# Teensy-Maxuino-Slave-A4988-stepper_shiel.net
KiCad netlist of a schematic drawn in EAGLE
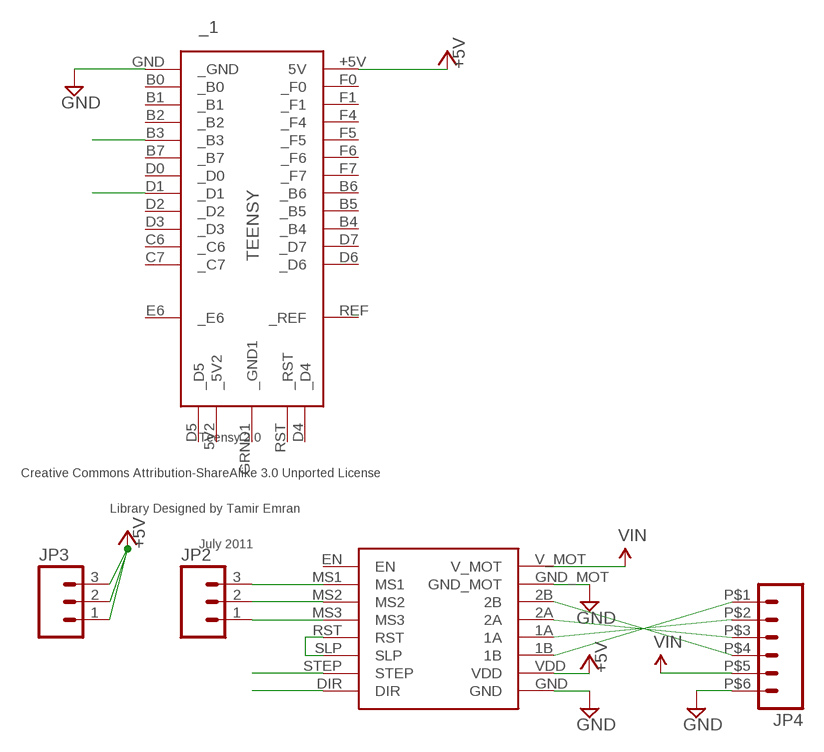
[diagram p0: schematic, sheet 1]

(export (version "E")
  (design (tool "Eeschema 10.0.6"))
  (components
    (comp (ref "JP2")
      (value "M03PTH")
      (footprint "eagle-import:1X03")
      (libsource (lib "eagle-import") (part "M03PTH"))
    )
    (comp (ref "JP3")
      (value "M03PTH")
      (footprint "eagle-import:1X03")
      (libsource (lib "eagle-import") (part "M03PTH"))
    )
    (comp (ref "JP4")
      (value "M06")
      (footprint "eagle-import:SPRINGTERMINAL-2.54MM-6")
      (libsource (lib "eagle-import") (part "M06"))
    )
    (comp (ref "U$1")
      (value "POLOLU_A4988")
      (footprint "eagle-import:POLOLU_A4988")
      (libsource (lib "eagle-import") (part "POLOLU_A4988"))
    )
    (comp (ref "_1")
      (value "TEENSY")
      (footprint "eagle-import:TEENSY")
      (libsource (lib "eagle-import") (part "TEENSY"))
    )
  )
  (nets
    (net (code "1") (name "+5V") (class "Default")
      (node (ref "JP3") (pin "1") (pinfunction "1_1") (pintype "passive"))
      (node (ref "JP3") (pin "2") (pinfunction "2_2") (pintype "passive"))
      (node (ref "JP3") (pin "3") (pinfunction "3_3") (pintype "passive"))
      (node (ref "U$1") (pin "VDD") (pinfunction "VDD_VDD") (pintype "bidirectional"))
      (node (ref "_1") (pin "+5V") (pinfunction "5V_+5V") (pintype "bidirectional"))
    )
    (net (code "2") (name "/DIR") (class "Default")
      (node (ref "U$1") (pin "DIR") (pinfunction "DIR_DIR") (pintype "bidirectional"))
      (node (ref "_1") (pin "D1") (pinfunction "_D1_D1") (pintype "bidirectional"))
    )
    (net (code "3") (name "/STEP") (class "Default")
      (node (ref "U$1") (pin "STEP") (pinfunction "STEP_STEP") (pintype "bidirectional"))
      (node (ref "_1") (pin "B3") (pinfunction "_B3_B3") (pintype "bidirectional"))
    )
    (net (code "4") (name "GND") (class "Default")
      (node (ref "JP4") (pin "P$6") (pinfunction "6_P$6") (pintype "passive"))
      (node (ref "U$1") (pin "GND") (pinfunction "GND_GND") (pintype "bidirectional"))
      (node (ref "U$1") (pin "GND_MOT") (pinfunction "GND_MOT_GND_MOT") (pintype "bidirectional"))
      (node (ref "_1") (pin "GND") (pinfunction "_GND_GND") (pintype "bidirectional"))
    )
    (net (code "5") (name "Net-(JP2-Pad1)") (class "Default")
      (node (ref "JP2") (pin "1") (pinfunction "1_1") (pintype "passive"))
      (node (ref "U$1") (pin "MS3") (pinfunction "MS3_MS3") (pintype "bidirectional"))
    )
    (net (code "6") (name "Net-(JP2-Pad2)") (class "Default")
      (node (ref "JP2") (pin "2") (pinfunction "2_2") (pintype "passive"))
      (node (ref "U$1") (pin "MS2") (pinfunction "MS2_MS2") (pintype "bidirectional"))
    )
    (net (code "7") (name "Net-(JP2-Pad3)") (class "Default")
      (node (ref "JP2") (pin "3") (pinfunction "3_3") (pintype "passive"))
      (node (ref "U$1") (pin "MS1") (pinfunction "MS1_MS1") (pintype "bidirectional"))
    )
    (net (code "8") (name "Net-(JP4-1)") (class "Default")
      (node (ref "JP4") (pin "P$1") (pinfunction "1_P$1") (pintype "passive"))
      (node (ref "U$1") (pin "1B") (pinfunction "1B_1B") (pintype "bidirectional"))
    )
    (net (code "9") (name "Net-(JP4-2)") (class "Default")
      (node (ref "JP4") (pin "P$2") (pinfunction "2_P$2") (pintype "passive"))
      (node (ref "U$1") (pin "1A") (pinfunction "1A_1A") (pintype "bidirectional"))
    )
    (net (code "10") (name "Net-(JP4-3)") (class "Default")
      (node (ref "JP4") (pin "P$3") (pinfunction "3_P$3") (pintype "passive"))
      (node (ref "U$1") (pin "2A") (pinfunction "2A_2A") (pintype "bidirectional"))
    )
    (net (code "11") (name "Net-(JP4-4)") (class "Default")
      (node (ref "JP4") (pin "P$4") (pinfunction "4_P$4") (pintype "passive"))
      (node (ref "U$1") (pin "2B") (pinfunction "2B_2B") (pintype "bidirectional"))
    )
    (net (code "12") (name "Net-(U$1-PadRST)") (class "Default")
      (node (ref "U$1") (pin "RST") (pinfunction "RST_RST") (pintype "bidirectional"))
      (node (ref "U$1") (pin "SLP") (pinfunction "SLP_SLP") (pintype "bidirectional"))
    )
    (net (code "13") (name "VIN") (class "Default")
      (node (ref "JP4") (pin "P$5") (pinfunction "5_P$5") (pintype "passive"))
      (node (ref "U$1") (pin "V_MOT") (pinfunction "V_MOT_V_MOT") (pintype "bidirectional"))
    )
    (net (code "14") (name "unconnected-(U$1-PadEN)") (class "Default")
      (node (ref "U$1") (pin "EN") (pinfunction "EN_EN") (pintype "bidirectional"))
    )
    (net (code "15") (name "unconnected-(_1-_5V2-Pad5V2)") (class "Default")
      (node (ref "_1") (pin "5V2") (pinfunction "_5V2_5V2") (pintype "bidirectional"))
    )
    (net (code "16") (name "unconnected-(_1-_B0-PadB0)") (class "Default")
      (node (ref "_1") (pin "B0") (pinfunction "_B0_B0") (pintype "bidirectional"))
    )
    (net (code "17") (name "unconnected-(_1-_B1-PadB1)") (class "Default")
      (node (ref "_1") (pin "B1") (pinfunction "_B1_B1") (pintype "bidirectional"))
    )
    (net (code "18") (name "unconnected-(_1-_B2-PadB2)") (class "Default")
      (node (ref "_1") (pin "B2") (pinfunction "_B2_B2") (pintype "bidirectional"))
    )
    (net (code "19") (name "unconnected-(_1-_B4-PadB4)") (class "Default")
      (node (ref "_1") (pin "B4") (pinfunction "_B4_B4") (pintype "bidirectional"))
    )
    (net (code "20") (name "unconnected-(_1-_B5-PadB5)") (class "Default")
      (node (ref "_1") (pin "B5") (pinfunction "_B5_B5") (pintype "bidirectional"))
    )
    (net (code "21") (name "unconnected-(_1-_B6-PadB6)") (class "Default")
      (node (ref "_1") (pin "B6") (pinfunction "_B6_B6") (pintype "bidirectional"))
    )
    (net (code "22") (name "unconnected-(_1-_B7-PadB7)") (class "Default")
      (node (ref "_1") (pin "B7") (pinfunction "_B7_B7") (pintype "bidirectional"))
    )
    (net (code "23") (name "unconnected-(_1-_C6-PadC6)") (class "Default")
      (node (ref "_1") (pin "C6") (pinfunction "_C6_C6") (pintype "bidirectional"))
    )
    (net (code "24") (name "unconnected-(_1-_C7-PadC7)") (class "Default")
      (node (ref "_1") (pin "C7") (pinfunction "_C7_C7") (pintype "bidirectional"))
    )
    (net (code "25") (name "unconnected-(_1-_D0-PadD0)") (class "Default")
      (node (ref "_1") (pin "D0") (pinfunction "_D0_D0") (pintype "bidirectional"))
    )
    (net (code "26") (name "unconnected-(_1-_D2-PadD2)") (class "Default")
      (node (ref "_1") (pin "D2") (pinfunction "_D2_D2") (pintype "bidirectional"))
    )
    (net (code "27") (name "unconnected-(_1-_D3-PadD3)") (class "Default")
      (node (ref "_1") (pin "D3") (pinfunction "_D3_D3") (pintype "bidirectional"))
    )
    (net (code "28") (name "unconnected-(_1-_D4-PadD4)") (class "Default")
      (node (ref "_1") (pin "D4") (pinfunction "_D4_D4") (pintype "bidirectional"))
    )
    (net (code "29") (name "unconnected-(_1-_D5-PadD5)") (class "Default")
      (node (ref "_1") (pin "D5") (pinfunction "_D5_D5") (pintype "bidirectional"))
    )
    (net (code "30") (name "unconnected-(_1-_D6-PadD6)") (class "Default")
      (node (ref "_1") (pin "D6") (pinfunction "_D6_D6") (pintype "bidirectional"))
    )
    (net (code "31") (name "unconnected-(_1-_D7-PadD7)") (class "Default")
      (node (ref "_1") (pin "D7") (pinfunction "_D7_D7") (pintype "bidirectional"))
    )
    (net (code "32") (name "unconnected-(_1-_E6-PadE6)") (class "Default")
      (node (ref "_1") (pin "E6") (pinfunction "_E6_E6") (pintype "bidirectional"))
    )
    (net (code "33") (name "unconnected-(_1-_F0-PadF0)") (class "Default")
      (node (ref "_1") (pin "F0") (pinfunction "_F0_F0") (pintype "bidirectional"))
    )
    (net (code "34") (name "unconnected-(_1-_F1-PadF1)") (class "Default")
      (node (ref "_1") (pin "F1") (pinfunction "_F1_F1") (pintype "bidirectional"))
    )
    (net (code "35") (name "unconnected-(_1-_F4-PadF4)") (class "Default")
      (node (ref "_1") (pin "F4") (pinfunction "_F4_F4") (pintype "bidirectional"))
    )
    (net (code "36") (name "unconnected-(_1-_F5-PadF5)") (class "Default")
      (node (ref "_1") (pin "F5") (pinfunction "_F5_F5") (pintype "bidirectional"))
    )
    (net (code "37") (name "unconnected-(_1-_F6-PadF6)") (class "Default")
      (node (ref "_1") (pin "F6") (pinfunction "_F6_F6") (pintype "bidirectional"))
    )
    (net (code "38") (name "unconnected-(_1-_F7-PadF7)") (class "Default")
      (node (ref "_1") (pin "F7") (pinfunction "_F7_F7") (pintype "bidirectional"))
    )
    (net (code "39") (name "unconnected-(_1-_GND1-PadGRND1)") (class "Default")
      (node (ref "_1") (pin "GRND1") (pinfunction "_GND1_GRND1") (pintype "bidirectional"))
    )
    (net (code "40") (name "unconnected-(_1-_REF-PadREF)") (class "Default")
      (node (ref "_1") (pin "REF") (pinfunction "_REF_REF") (pintype "bidirectional"))
    )
    (net (code "41") (name "unconnected-(_1-_RST-PadRST)") (class "Default")
      (node (ref "_1") (pin "RST") (pinfunction "_RST_RST") (pintype "bidirectional"))
    )
  )
)
